# adafruit_tlc59711_v1.net
KiCad netlist of a schematic drawn in EAGLE
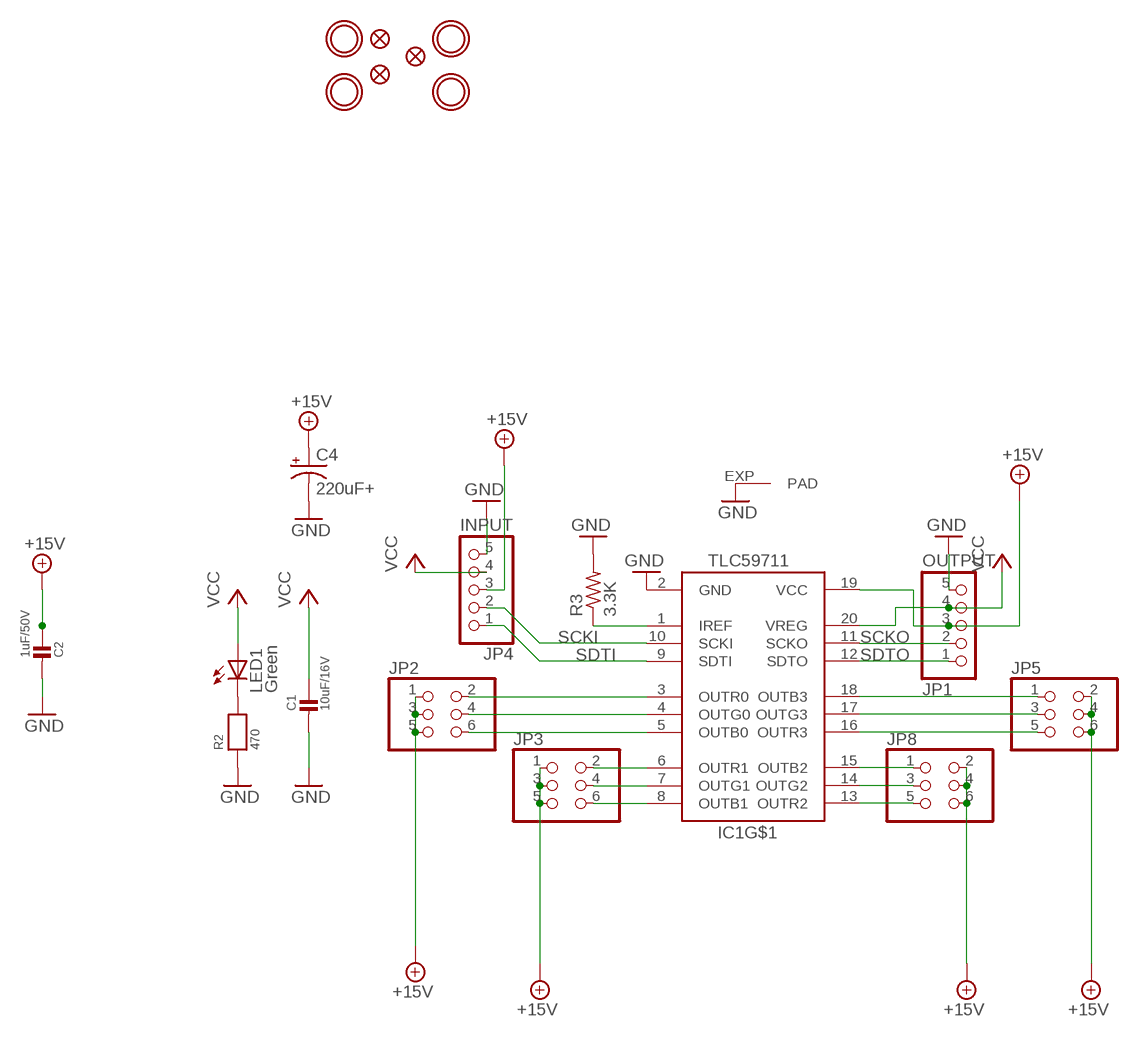
[diagram p0: schematic, sheet 1]

(export (version "E")
  (design (tool "Eeschema 10.0.6"))
  (components
    (comp (ref "C1")
      (value "10uF/16V")
      (footprint "eagle-import:0805")
      (libsource (lib "eagle-import") (part "CAP_CERAMIC0805"))
    )
    (comp (ref "C2")
      (value "1uF/50V")
      (footprint "eagle-import:0805")
      (libsource (lib "eagle-import") (part "CAP_CERAMIC0805"))
    )
    (comp (ref "C4")
      (value "220uF+")
      (footprint "eagle-import:E2,5-7")
      (libsource (lib "eagle-import") (part "CPOL-USE2.5-7"))
    )
    (comp (ref "FID1")
      (value "FIDUCIAL\"\"")
      (footprint "eagle-import:FIDUCIAL_1MM")
      (libsource (lib "eagle-import") (part "FIDUCIAL{dblquote}{dblquote}"))
    )
    (comp (ref "FID2")
      (value "FIDUCIAL\"\"")
      (footprint "eagle-import:FIDUCIAL_1MM")
      (libsource (lib "eagle-import") (part "FIDUCIAL{dblquote}{dblquote}"))
    )
    (comp (ref "FID3")
      (value "FIDUCIAL\"\"")
      (footprint "eagle-import:FIDUCIAL_1MM")
      (libsource (lib "eagle-import") (part "FIDUCIAL{dblquote}{dblquote}"))
    )
    (comp (ref "IC1")
      (value "TLC59711")
      (footprint "eagle-import:HTSSOP20DAP")
      (libsource (lib "eagle-import") (part "TLC59711"))
    )
    (comp (ref "JP1")
      (value "OUTPUT")
      (footprint "eagle-import:1X05_ROUND_70")
      (libsource (lib "eagle-import") (part "HEADER-1X570MIL"))
    )
    (comp (ref "JP2")
      (value "HEADER-2X3")
      (footprint "eagle-import:2X03_ROUND_70MIL")
      (libsource (lib "eagle-import") (part "HEADER-2X3"))
    )
    (comp (ref "JP3")
      (value "HEADER-2X3")
      (footprint "eagle-import:2X03_ROUND_70MIL")
      (libsource (lib "eagle-import") (part "HEADER-2X3"))
    )
    (comp (ref "JP4")
      (value "INPUT")
      (footprint "eagle-import:1X05_ROUND_70")
      (libsource (lib "eagle-import") (part "HEADER-1X570MIL"))
    )
    (comp (ref "JP5")
      (value "HEADER-2X3")
      (footprint "eagle-import:2X03_ROUND_70MIL")
      (libsource (lib "eagle-import") (part "HEADER-2X3"))
    )
    (comp (ref "JP8")
      (value "HEADER-2X3")
      (footprint "eagle-import:2X03_ROUND_70MIL")
      (libsource (lib "eagle-import") (part "HEADER-2X3"))
    )
    (comp (ref "LED1")
      (value "Green")
      (footprint "eagle-import:CHIP-LED0805")
      (libsource (lib "eagle-import") (part "LEDCHIP-LED0805"))
    )
    (comp (ref "R2")
      (value "470")
      (footprint "eagle-import:0805")
      (libsource (lib "eagle-import") (part "RESISTOR0805"))
    )
    (comp (ref "R3")
      (value "3.3K")
      (footprint "eagle-import:0805-THM-7")
      (libsource (lib "eagle-import") (part "R-US_FLIPFLOP7"))
    )
    (comp (ref "U$1")
      (value "MOUNTINGHOLE2.5")
      (footprint "eagle-import:MOUNTINGHOLE_2.5_PLATED")
      (libsource (lib "eagle-import") (part "MOUNTINGHOLE2.5"))
    )
    (comp (ref "U$2")
      (value "MOUNTINGHOLE2.5")
      (footprint "eagle-import:MOUNTINGHOLE_2.5_PLATED")
      (libsource (lib "eagle-import") (part "MOUNTINGHOLE2.5"))
    )
    (comp (ref "U$3")
      (value "MOUNTINGHOLE2.5")
      (footprint "eagle-import:MOUNTINGHOLE_2.5_PLATED")
      (libsource (lib "eagle-import") (part "MOUNTINGHOLE2.5"))
    )
    (comp (ref "U$4")
      (value "MOUNTINGHOLE2.5")
      (footprint "eagle-import:MOUNTINGHOLE_2.5_PLATED")
      (libsource (lib "eagle-import") (part "MOUNTINGHOLE2.5"))
    )
  )
  (nets
    (net (code "1") (name "+15V") (class "Default")
      (node (ref "C2") (pin "1") (pinfunction "P$1_1") (pintype "passive"))
      (node (ref "C4") (pin "+") (pinfunction "+_+") (pintype "passive"))
      (node (ref "IC1") (pin "19") (pinfunction "VCC_19") (pintype "power_in"))
      (node (ref "JP1") (pin "3") (pinfunction "3_3") (pintype "passive"))
      (node (ref "JP2") (pin "1") (pinfunction "1_1") (pintype "passive"))
      (node (ref "JP2") (pin "3") (pinfunction "3_3") (pintype "passive"))
      (node (ref "JP2") (pin "5") (pinfunction "5_5") (pintype "passive"))
      (node (ref "JP3") (pin "1") (pinfunction "1_1") (pintype "passive"))
      (node (ref "JP3") (pin "3") (pinfunction "3_3") (pintype "passive"))
      (node (ref "JP3") (pin "5") (pinfunction "5_5") (pintype "passive"))
      (node (ref "JP4") (pin "3") (pinfunction "3_3") (pintype "passive"))
      (node (ref "JP5") (pin "2") (pinfunction "2_2") (pintype "passive"))
      (node (ref "JP5") (pin "4") (pinfunction "4_4") (pintype "passive"))
      (node (ref "JP5") (pin "6") (pinfunction "6_6") (pintype "passive"))
      (node (ref "JP8") (pin "2") (pinfunction "2_2") (pintype "passive"))
      (node (ref "JP8") (pin "4") (pinfunction "4_4") (pintype "passive"))
      (node (ref "JP8") (pin "6") (pinfunction "6_6") (pintype "passive"))
    )
    (net (code "2") (name "/SCKI") (class "Default")
      (node (ref "IC1") (pin "10") (pinfunction "SCKI_10") (pintype "input"))
      (node (ref "JP4") (pin "2") (pinfunction "2_2") (pintype "passive"))
    )
    (net (code "3") (name "/SCKO") (class "Default")
      (node (ref "IC1") (pin "11") (pinfunction "SCKO_11") (pintype "output"))
      (node (ref "JP1") (pin "2") (pinfunction "2_2") (pintype "passive"))
    )
    (net (code "4") (name "/SDTI") (class "Default")
      (node (ref "IC1") (pin "9") (pinfunction "SDTI_9") (pintype "input"))
      (node (ref "JP4") (pin "1") (pinfunction "1_1") (pintype "passive"))
    )
    (net (code "5") (name "/SDTO") (class "Default")
      (node (ref "IC1") (pin "12") (pinfunction "SDTO_12") (pintype "output"))
      (node (ref "JP1") (pin "1") (pinfunction "1_1") (pintype "passive"))
    )
    (net (code "6") (name "GND") (class "Default")
      (node (ref "C1") (pin "2") (pinfunction "P$2_2") (pintype "passive"))
      (node (ref "C2") (pin "2") (pinfunction "P$2_2") (pintype "passive"))
      (node (ref "C4") (pin "-") (pinfunction "-_-") (pintype "passive"))
      (node (ref "IC1") (pin "2") (pinfunction "GND_2") (pintype "power_in"))
      (node (ref "IC1") (pin "EXP") (pinfunction "PAD_EXP") (pintype "passive"))
      (node (ref "JP1") (pin "5") (pinfunction "5_5") (pintype "passive"))
      (node (ref "JP4") (pin "5") (pinfunction "5_5") (pintype "passive"))
      (node (ref "R2") (pin "1") (pinfunction "1_1") (pintype "passive"))
      (node (ref "R3") (pin "2") (pinfunction "2_2") (pintype "passive"))
    )
    (net (code "7") (name "Net-(IC1A-IREF)") (class "Default")
      (node (ref "IC1") (pin "1") (pinfunction "IREF_1") (pintype "bidirectional"))
      (node (ref "R3") (pin "1") (pinfunction "1_1") (pintype "passive"))
    )
    (net (code "8") (name "Net-(IC1A-OUTB0)") (class "Default")
      (node (ref "IC1") (pin "5") (pinfunction "OUTB0_5") (pintype "open_collector"))
      (node (ref "JP2") (pin "6") (pinfunction "6_6") (pintype "passive"))
    )
    (net (code "9") (name "Net-(IC1A-OUTB1)") (class "Default")
      (node (ref "IC1") (pin "8") (pinfunction "OUTB1_8") (pintype "open_collector"))
      (node (ref "JP3") (pin "6") (pinfunction "6_6") (pintype "passive"))
    )
    (net (code "10") (name "Net-(IC1A-OUTB2)") (class "Default")
      (node (ref "IC1") (pin "15") (pinfunction "OUTB2_15") (pintype "open_collector"))
      (node (ref "JP8") (pin "1") (pinfunction "1_1") (pintype "passive"))
    )
    (net (code "11") (name "Net-(IC1A-OUTB3)") (class "Default")
      (node (ref "IC1") (pin "18") (pinfunction "OUTB3_18") (pintype "open_collector"))
      (node (ref "JP5") (pin "1") (pinfunction "1_1") (pintype "passive"))
    )
    (net (code "12") (name "Net-(IC1A-OUTG0)") (class "Default")
      (node (ref "IC1") (pin "4") (pinfunction "OUTG0_4") (pintype "open_collector"))
      (node (ref "JP2") (pin "4") (pinfunction "4_4") (pintype "passive"))
    )
    (net (code "13") (name "Net-(IC1A-OUTG1)") (class "Default")
      (node (ref "IC1") (pin "7") (pinfunction "OUTG1_7") (pintype "open_collector"))
      (node (ref "JP3") (pin "4") (pinfunction "4_4") (pintype "passive"))
    )
    (net (code "14") (name "Net-(IC1A-OUTG2)") (class "Default")
      (node (ref "IC1") (pin "14") (pinfunction "OUTG2_14") (pintype "open_collector"))
      (node (ref "JP8") (pin "3") (pinfunction "3_3") (pintype "passive"))
    )
    (net (code "15") (name "Net-(IC1A-OUTG3)") (class "Default")
      (node (ref "IC1") (pin "17") (pinfunction "OUTG3_17") (pintype "open_collector"))
      (node (ref "JP5") (pin "3") (pinfunction "3_3") (pintype "passive"))
    )
    (net (code "16") (name "Net-(IC1A-OUTR0)") (class "Default")
      (node (ref "IC1") (pin "3") (pinfunction "OUTR0_3") (pintype "open_collector"))
      (node (ref "JP2") (pin "2") (pinfunction "2_2") (pintype "passive"))
    )
    (net (code "17") (name "Net-(IC1A-OUTR1)") (class "Default")
      (node (ref "IC1") (pin "6") (pinfunction "OUTR1_6") (pintype "open_collector"))
      (node (ref "JP3") (pin "2") (pinfunction "2_2") (pintype "passive"))
    )
    (net (code "18") (name "Net-(IC1A-OUTR2)") (class "Default")
      (node (ref "IC1") (pin "13") (pinfunction "OUTR2_13") (pintype "open_collector"))
      (node (ref "JP8") (pin "5") (pinfunction "5_5") (pintype "passive"))
    )
    (net (code "19") (name "Net-(IC1A-OUTR3)") (class "Default")
      (node (ref "IC1") (pin "16") (pinfunction "OUTR3_16") (pintype "open_collector"))
      (node (ref "JP5") (pin "5") (pinfunction "5_5") (pintype "passive"))
    )
    (net (code "20") (name "Net-(LED1-PadC)") (class "Default")
      (node (ref "LED1") (pin "C") (pinfunction "C_C") (pintype "passive"))
      (node (ref "R2") (pin "2") (pinfunction "2_2") (pintype "passive"))
    )
    (net (code "21") (name "VCC") (class "Default")
      (node (ref "C1") (pin "1") (pinfunction "P$1_1") (pintype "passive"))
      (node (ref "IC1") (pin "20") (pinfunction "VREG_20") (pintype "bidirectional"))
      (node (ref "JP1") (pin "4") (pinfunction "4_4") (pintype "passive"))
      (node (ref "JP4") (pin "4") (pinfunction "4_4") (pintype "passive"))
      (node (ref "LED1") (pin "A") (pinfunction "A_A") (pintype "passive"))
    )
  )
)
